# TDT_CableTester.net
KiCad netlist of a schematic drawn in EAGLE
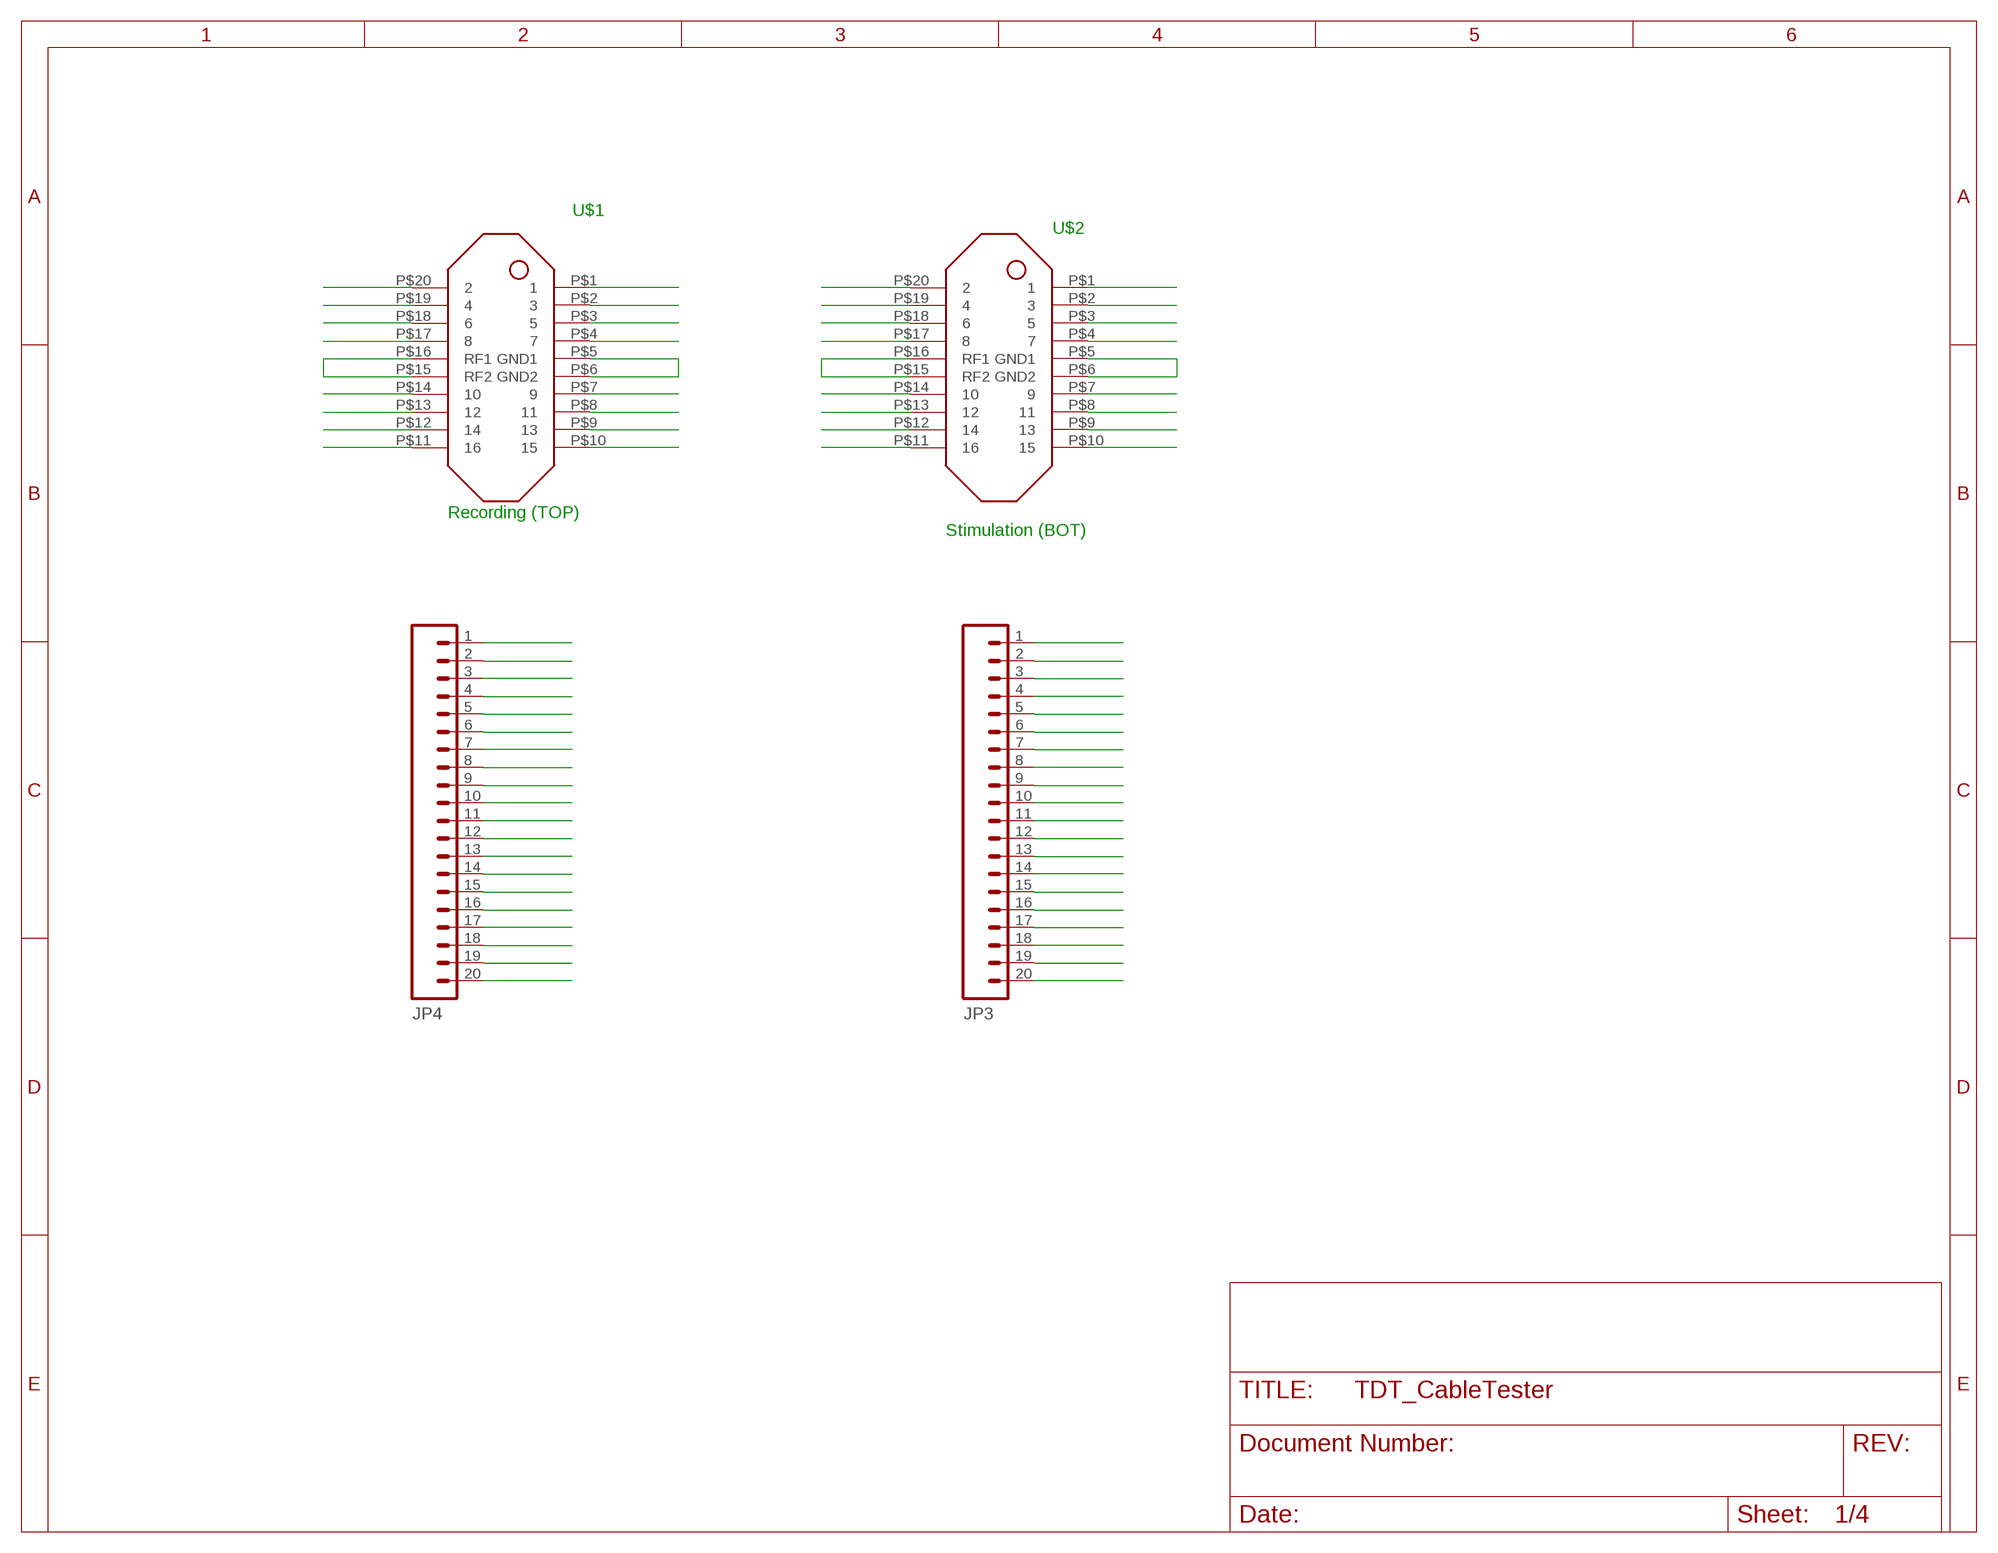
[diagram p0: schematic, sheet 1]
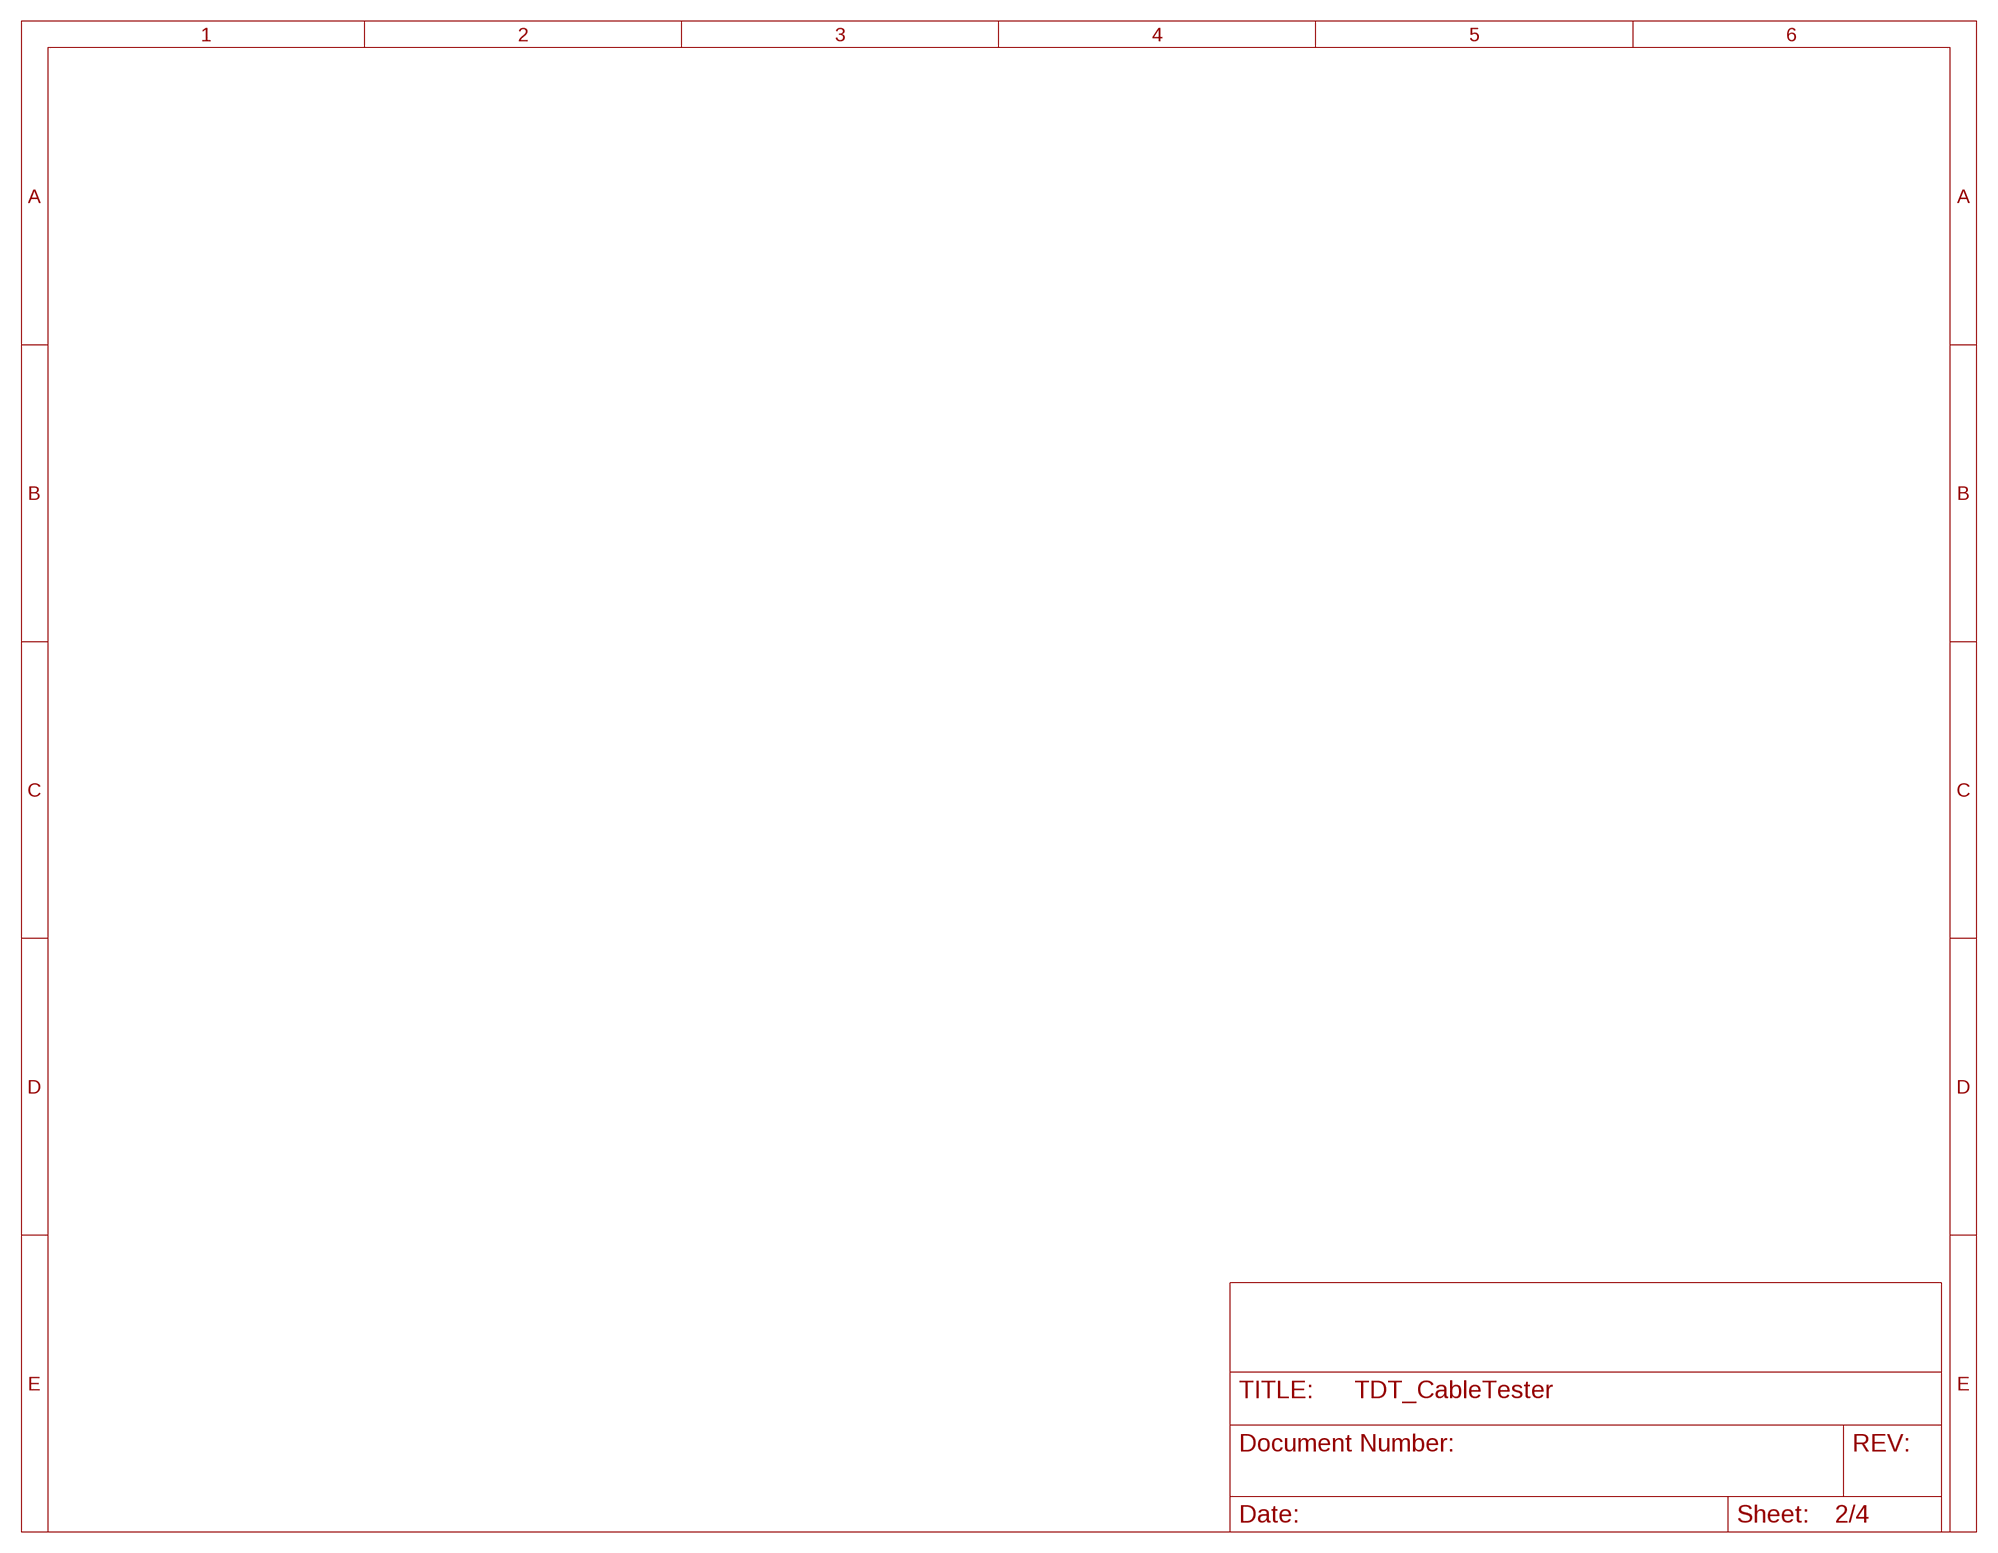
[diagram p1: schematic, sheet 2]

(export (version "E")
  (design (tool "Eeschema 10.0.6"))
  (components
    (comp (ref "JP3")
      (value "M20")
      (footprint "eagle-import:1X20")
      (libsource (lib "eagle-import") (part "M20"))
    )
    (comp (ref "JP4")
      (value "M20")
      (footprint "eagle-import:1X20")
      (libsource (lib "eagle-import") (part "M20"))
    )
    (comp (ref "U$1")
      (value "DF30_HEADER")
      (footprint "eagle-import:DF30FC-20DP-0.4V")
      (libsource (lib "eagle-import") (part "DF30_HEADER"))
    )
    (comp (ref "U$2")
      (value "DF30_HEADER")
      (footprint "eagle-import:DF30FC-20DP-0.4V")
      (libsource (lib "eagle-import") (part "DF30_HEADER"))
    )
  )
  (nets
    (net (code "1") (name "B1") (class "Default")
      (node (ref "JP3") (pin "1") (pinfunction "1_1") (pintype "passive"))
      (node (ref "U$2") (pin "P$1") (pinfunction "1_P$1") (pintype "bidirectional"))
    )
    (net (code "2") (name "B2") (class "Default")
      (node (ref "JP3") (pin "2") (pinfunction "2_2") (pintype "passive"))
      (node (ref "U$2") (pin "P$20") (pinfunction "2_P$20") (pintype "bidirectional"))
    )
    (net (code "3") (name "B3") (class "Default")
      (node (ref "JP3") (pin "3") (pinfunction "3_3") (pintype "passive"))
      (node (ref "U$2") (pin "P$2") (pinfunction "3_P$2") (pintype "bidirectional"))
    )
    (net (code "4") (name "B4") (class "Default")
      (node (ref "JP3") (pin "4") (pinfunction "4_4") (pintype "passive"))
      (node (ref "U$2") (pin "P$19") (pinfunction "4_P$19") (pintype "bidirectional"))
    )
    (net (code "5") (name "B5") (class "Default")
      (node (ref "JP3") (pin "5") (pinfunction "5_5") (pintype "passive"))
      (node (ref "U$2") (pin "P$3") (pinfunction "5_P$3") (pintype "bidirectional"))
    )
    (net (code "6") (name "B6") (class "Default")
      (node (ref "JP3") (pin "6") (pinfunction "6_6") (pintype "passive"))
      (node (ref "U$2") (pin "P$18") (pinfunction "6_P$18") (pintype "bidirectional"))
    )
    (net (code "7") (name "B7") (class "Default")
      (node (ref "JP3") (pin "7") (pinfunction "7_7") (pintype "passive"))
      (node (ref "U$2") (pin "P$4") (pinfunction "7_P$4") (pintype "bidirectional"))
    )
    (net (code "8") (name "B8") (class "Default")
      (node (ref "JP3") (pin "8") (pinfunction "8_8") (pintype "passive"))
      (node (ref "U$2") (pin "P$17") (pinfunction "8_P$17") (pintype "bidirectional"))
    )
    (net (code "9") (name "B9") (class "Default")
      (node (ref "JP3") (pin "9") (pinfunction "9_9") (pintype "passive"))
      (node (ref "U$2") (pin "P$7") (pinfunction "9_P$7") (pintype "bidirectional"))
    )
    (net (code "10") (name "B10") (class "Default")
      (node (ref "JP3") (pin "10") (pinfunction "10_10") (pintype "passive"))
      (node (ref "U$2") (pin "P$14") (pinfunction "10_P$14") (pintype "bidirectional"))
    )
    (net (code "11") (name "B11") (class "Default")
      (node (ref "JP3") (pin "11") (pinfunction "11_11") (pintype "passive"))
      (node (ref "U$2") (pin "P$8") (pinfunction "11_P$8") (pintype "bidirectional"))
    )
    (net (code "12") (name "B12") (class "Default")
      (node (ref "JP3") (pin "12") (pinfunction "12_12") (pintype "passive"))
      (node (ref "U$2") (pin "P$13") (pinfunction "12_P$13") (pintype "bidirectional"))
    )
    (net (code "13") (name "B13") (class "Default")
      (node (ref "JP3") (pin "13") (pinfunction "13_13") (pintype "passive"))
      (node (ref "U$2") (pin "P$9") (pinfunction "13_P$9") (pintype "bidirectional"))
    )
    (net (code "14") (name "B14") (class "Default")
      (node (ref "JP3") (pin "14") (pinfunction "14_14") (pintype "passive"))
      (node (ref "U$2") (pin "P$12") (pinfunction "14_P$12") (pintype "bidirectional"))
    )
    (net (code "15") (name "B15") (class "Default")
      (node (ref "JP3") (pin "15") (pinfunction "15_15") (pintype "passive"))
      (node (ref "U$2") (pin "P$10") (pinfunction "15_P$10") (pintype "bidirectional"))
    )
    (net (code "16") (name "B16") (class "Default")
      (node (ref "JP3") (pin "16") (pinfunction "16_16") (pintype "passive"))
      (node (ref "U$2") (pin "P$11") (pinfunction "16_P$11") (pintype "bidirectional"))
    )
    (net (code "17") (name "BG1") (class "Default")
      (node (ref "JP3") (pin "19") (pinfunction "19_19") (pintype "passive"))
      (node (ref "U$2") (pin "P$5") (pinfunction "GND1_P$5") (pintype "bidirectional"))
      (node (ref "U$2") (pin "P$6") (pinfunction "GND2_P$6") (pintype "bidirectional"))
    )
    (net (code "18") (name "BRF1") (class "Default")
      (node (ref "JP3") (pin "17") (pinfunction "17_17") (pintype "passive"))
      (node (ref "U$2") (pin "P$15") (pinfunction "RF2_P$15") (pintype "bidirectional"))
      (node (ref "U$2") (pin "P$16") (pinfunction "RF1_P$16") (pintype "bidirectional"))
    )
    (net (code "19") (name "T1") (class "Default")
      (node (ref "JP4") (pin "1") (pinfunction "1_1") (pintype "passive"))
      (node (ref "U$1") (pin "P$1") (pinfunction "1_P$1") (pintype "bidirectional"))
    )
    (net (code "20") (name "T2") (class "Default")
      (node (ref "JP4") (pin "2") (pinfunction "2_2") (pintype "passive"))
      (node (ref "U$1") (pin "P$20") (pinfunction "2_P$20") (pintype "bidirectional"))
    )
    (net (code "21") (name "T3") (class "Default")
      (node (ref "JP4") (pin "3") (pinfunction "3_3") (pintype "passive"))
      (node (ref "U$1") (pin "P$2") (pinfunction "3_P$2") (pintype "bidirectional"))
    )
    (net (code "22") (name "T4") (class "Default")
      (node (ref "JP4") (pin "4") (pinfunction "4_4") (pintype "passive"))
      (node (ref "U$1") (pin "P$19") (pinfunction "4_P$19") (pintype "bidirectional"))
    )
    (net (code "23") (name "T5") (class "Default")
      (node (ref "JP4") (pin "5") (pinfunction "5_5") (pintype "passive"))
      (node (ref "U$1") (pin "P$3") (pinfunction "5_P$3") (pintype "bidirectional"))
    )
    (net (code "24") (name "T6") (class "Default")
      (node (ref "JP4") (pin "6") (pinfunction "6_6") (pintype "passive"))
      (node (ref "U$1") (pin "P$18") (pinfunction "6_P$18") (pintype "bidirectional"))
    )
    (net (code "25") (name "T7") (class "Default")
      (node (ref "JP4") (pin "7") (pinfunction "7_7") (pintype "passive"))
      (node (ref "U$1") (pin "P$4") (pinfunction "7_P$4") (pintype "bidirectional"))
    )
    (net (code "26") (name "T8") (class "Default")
      (node (ref "JP4") (pin "8") (pinfunction "8_8") (pintype "passive"))
      (node (ref "U$1") (pin "P$17") (pinfunction "8_P$17") (pintype "bidirectional"))
    )
    (net (code "27") (name "T9") (class "Default")
      (node (ref "JP4") (pin "9") (pinfunction "9_9") (pintype "passive"))
      (node (ref "U$1") (pin "P$7") (pinfunction "9_P$7") (pintype "bidirectional"))
    )
    (net (code "28") (name "T10") (class "Default")
      (node (ref "JP4") (pin "10") (pinfunction "10_10") (pintype "passive"))
      (node (ref "U$1") (pin "P$14") (pinfunction "10_P$14") (pintype "bidirectional"))
    )
    (net (code "29") (name "T11") (class "Default")
      (node (ref "JP4") (pin "11") (pinfunction "11_11") (pintype "passive"))
      (node (ref "U$1") (pin "P$8") (pinfunction "11_P$8") (pintype "bidirectional"))
    )
    (net (code "30") (name "T12") (class "Default")
      (node (ref "JP4") (pin "12") (pinfunction "12_12") (pintype "passive"))
      (node (ref "U$1") (pin "P$13") (pinfunction "12_P$13") (pintype "bidirectional"))
    )
    (net (code "31") (name "T13") (class "Default")
      (node (ref "JP4") (pin "13") (pinfunction "13_13") (pintype "passive"))
      (node (ref "U$1") (pin "P$9") (pinfunction "13_P$9") (pintype "bidirectional"))
    )
    (net (code "32") (name "T14") (class "Default")
      (node (ref "JP4") (pin "14") (pinfunction "14_14") (pintype "passive"))
      (node (ref "U$1") (pin "P$12") (pinfunction "14_P$12") (pintype "bidirectional"))
    )
    (net (code "33") (name "T15") (class "Default")
      (node (ref "JP4") (pin "15") (pinfunction "15_15") (pintype "passive"))
      (node (ref "U$1") (pin "P$10") (pinfunction "15_P$10") (pintype "bidirectional"))
    )
    (net (code "34") (name "T16") (class "Default")
      (node (ref "JP4") (pin "16") (pinfunction "16_16") (pintype "passive"))
      (node (ref "U$1") (pin "P$11") (pinfunction "16_P$11") (pintype "bidirectional"))
    )
    (net (code "35") (name "TG1") (class "Default")
      (node (ref "JP4") (pin "19") (pinfunction "19_19") (pintype "passive"))
      (node (ref "U$1") (pin "P$5") (pinfunction "GND1_P$5") (pintype "bidirectional"))
      (node (ref "U$1") (pin "P$6") (pinfunction "GND2_P$6") (pintype "bidirectional"))
    )
    (net (code "36") (name "TRF1") (class "Default")
      (node (ref "JP4") (pin "17") (pinfunction "17_17") (pintype "passive"))
      (node (ref "U$1") (pin "P$15") (pinfunction "RF2_P$15") (pintype "bidirectional"))
      (node (ref "U$1") (pin "P$16") (pinfunction "RF1_P$16") (pintype "bidirectional"))
    )
    (net (code "37") (name "unconnected-(JP3-Pad18)") (class "Default")
      (node (ref "JP3") (pin "18") (pinfunction "18_18") (pintype "passive"))
    )
    (net (code "38") (name "unconnected-(JP3-Pad20)") (class "Default")
      (node (ref "JP3") (pin "20") (pinfunction "20_20") (pintype "passive"))
    )
    (net (code "39") (name "unconnected-(JP4-Pad18)") (class "Default")
      (node (ref "JP4") (pin "18") (pinfunction "18_18") (pintype "passive"))
    )
    (net (code "40") (name "unconnected-(JP4-Pad20)") (class "Default")
      (node (ref "JP4") (pin "20") (pinfunction "20_20") (pintype "passive"))
    )
  )
)
